# LB_i11_Pressure_Sensor-v03_4_4.net
KiCad netlist of a schematic drawn in EAGLE
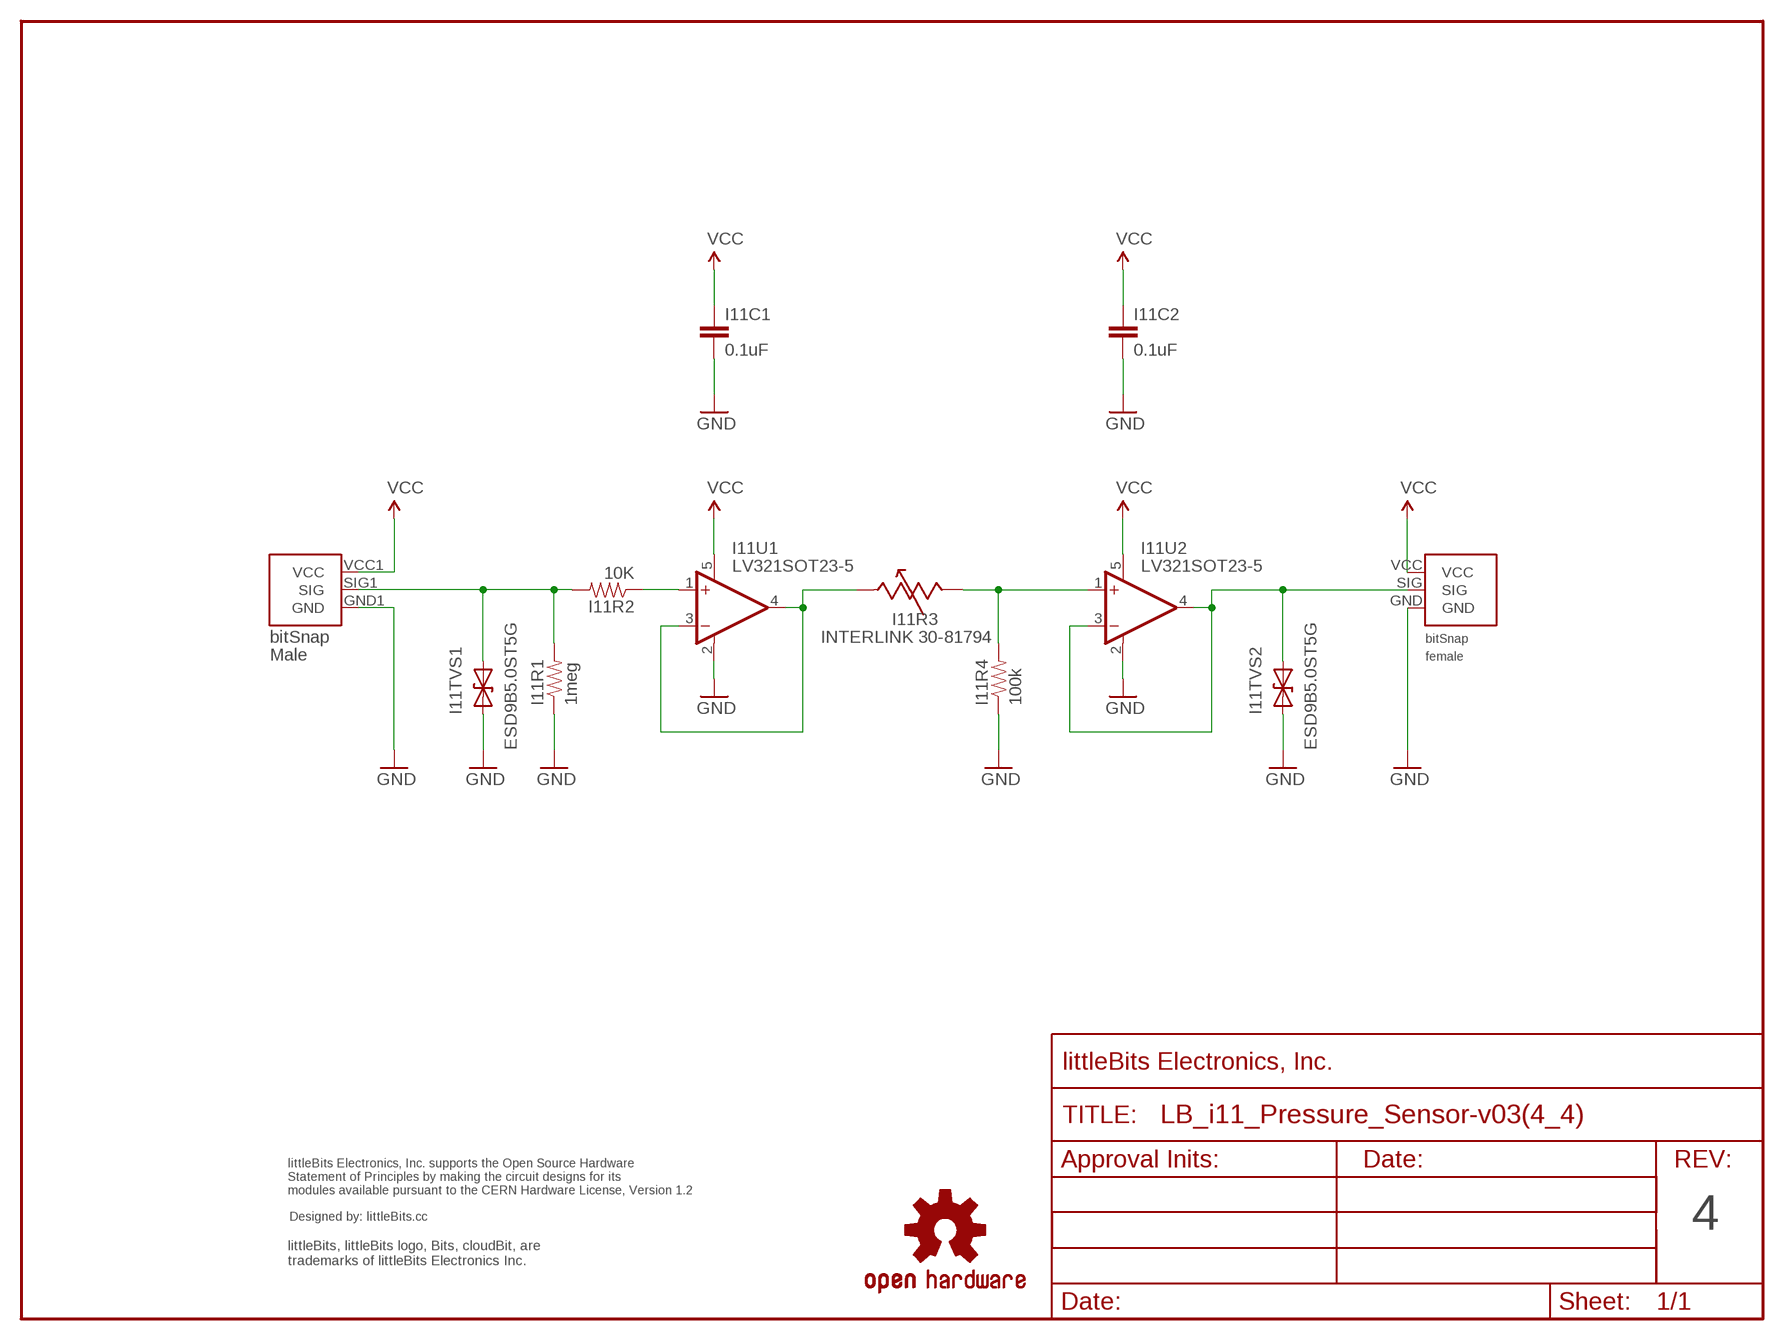
[diagram p0: schematic, sheet 1]

(export (version "E")
  (design (tool "Eeschema 10.0.6"))
  (components
    (comp (ref "FRAME1")
      (value "FRAME-LETTER-OHWOHW")
      (footprint "eagle-import:FABDWG01-OHW")
      (libsource (lib "eagle-import") (part "FRAME-LETTER-OHWOHW"))
    )
    (comp (ref "I11BSF1")
      (value "BITSNAP_V03_FEMALE")
      (footprint "eagle-import:BITSNAP_V03_FEMALE")
      (libsource (lib "eagle-import") (part "BITSNAP_V03_FEMALE"))
    )
    (comp (ref "I11BSM1")
      (value "BITSNAP_V03_MALE")
      (footprint "eagle-import:BITSNAP_V03_MALE")
      (libsource (lib "eagle-import") (part "BITSNAP_V03_MALE"))
    )
    (comp (ref "I11C1")
      (value "0.1uF")
      (footprint "eagle-import:0603-CAP")
      (libsource (lib "eagle-import") (part "CAP0603-CAP"))
    )
    (comp (ref "I11C2")
      (value "0.1uF")
      (footprint "eagle-import:0603-CAP")
      (libsource (lib "eagle-import") (part "CAP0603-CAP"))
    )
    (comp (ref "I11R1")
      (value "1meg")
      (footprint "eagle-import:RES-0603")
      (libsource (lib "eagle-import") (part "RESISTOR0603"))
    )
    (comp (ref "I11R2")
      (value "10K")
      (footprint "eagle-import:RES-0603")
      (libsource (lib "eagle-import") (part "RESISTOR0603"))
    )
    (comp (ref "I11R3")
      (value "INTERLINK 30-81794")
      (footprint "eagle-import:FSR-SMD")
      (libsource (lib "eagle-import") (part "FSR-SMD"))
    )
    (comp (ref "I11R4")
      (value "100k")
      (footprint "eagle-import:0603-RES")
      (libsource (lib "eagle-import") (part "RESISTOR0603-RES"))
    )
    (comp (ref "I11TVS1")
      (value "ESD9B5.0ST5G")
      (footprint "eagle-import:SOD-923")
      (fields (field (name "LB_PN") "?") (field (name "V_CLAMP") "?") (field (name "V_OPERATION") "5V"))
      (libsource (lib "eagle-import") (part "DIODE-TVSSOD-923"))
    )
    (comp (ref "I11TVS2")
      (value "ESD9B5.0ST5G")
      (footprint "eagle-import:SOD-923")
      (fields (field (name "LB_PN") "?") (field (name "V_CLAMP") "?") (field (name "V_OPERATION") "5V"))
      (libsource (lib "eagle-import") (part "DIODE-TVSSOD-923"))
    )
    (comp (ref "I11U1")
      (value "LV321SOT23-5")
      (footprint "eagle-import:SOT23-5")
      (libsource (lib "eagle-import") (part "LV321SOT23-5"))
    )
    (comp (ref "I11U2")
      (value "LV321SOT23-5")
      (footprint "eagle-import:SOT23-5")
      (libsource (lib "eagle-import") (part "LV321SOT23-5"))
    )
    (comp (ref "U$1")
      (value "OSHW-LOGOL")
      (footprint "eagle-import:OSHW-LOGO-L")
      (libsource (lib "eagle-import") (part "OSHW-LOGOL"))
    )
    (comp (ref "U$7")
      (value "LB_CREDITS")
      (footprint "eagle-import:OSHWCREDIT")
      (libsource (lib "eagle-import") (part "LB_CREDITS"))
    )
  )
  (nets
    (net (code "1") (name "GND") (class "Default")
      (node (ref "I11BSF1") (pin "GND") (pinfunction "GND_GND") (pintype "bidirectional"))
      (node (ref "I11BSM1") (pin "GND1") (pinfunction "GND_GND1") (pintype "bidirectional"))
      (node (ref "I11C1") (pin "2") (pinfunction "2_2") (pintype "passive"))
      (node (ref "I11C2") (pin "2") (pinfunction "2_2") (pintype "passive"))
      (node (ref "I11R1") (pin "1") (pinfunction "1_1") (pintype "passive"))
      (node (ref "I11R4") (pin "1") (pinfunction "1_1") (pintype "passive"))
      (node (ref "I11TVS1") (pin "1") (pinfunction "A_1") (pintype "passive"))
      (node (ref "I11TVS2") (pin "1") (pinfunction "A_1") (pintype "passive"))
      (node (ref "I11U1") (pin "2") (pinfunction "V-_2") (pintype "power_in"))
      (node (ref "I11U2") (pin "2") (pinfunction "V-_2") (pintype "power_in"))
    )
    (net (code "2") (name "Net-(I11BSM1-SIG)") (class "Default")
      (node (ref "I11BSM1") (pin "SIG1") (pinfunction "SIG_SIG1") (pintype "bidirectional"))
      (node (ref "I11R1") (pin "2") (pinfunction "2_2") (pintype "passive"))
      (node (ref "I11R2") (pin "2") (pinfunction "2_2") (pintype "passive"))
      (node (ref "I11TVS1") (pin "2") (pinfunction "C_2") (pintype "passive"))
    )
    (net (code "3") (name "Net-(I11R3-A)") (class "Default")
      (node (ref "I11R3") (pin "2") (pinfunction "A_2") (pintype "passive"))
      (node (ref "I11R4") (pin "2") (pinfunction "2_2") (pintype "passive"))
      (node (ref "I11U2") (pin "1") (pinfunction "+IN_1") (pintype "input"))
    )
    (net (code "4") (name "Net-(I11TVS2-C)") (class "Default")
      (node (ref "I11BSF1") (pin "SIG") (pinfunction "SIG_SIG") (pintype "bidirectional"))
      (node (ref "I11TVS2") (pin "2") (pinfunction "C_2") (pintype "passive"))
      (node (ref "I11U2") (pin "3") (pinfunction "-IN_3") (pintype "input"))
      (node (ref "I11U2") (pin "4") (pinfunction "OUT_4") (pintype "output"))
    )
    (net (code "5") (name "Net-(I11U1-+IN)") (class "Default")
      (node (ref "I11R2") (pin "1") (pinfunction "1_1") (pintype "passive"))
      (node (ref "I11U1") (pin "1") (pinfunction "+IN_1") (pintype "input"))
    )
    (net (code "6") (name "Net-(I11U1--IN)") (class "Default")
      (node (ref "I11R3") (pin "1") (pinfunction "1_1") (pintype "passive"))
      (node (ref "I11U1") (pin "3") (pinfunction "-IN_3") (pintype "input"))
      (node (ref "I11U1") (pin "4") (pinfunction "OUT_4") (pintype "output"))
    )
    (net (code "7") (name "VCC") (class "Default")
      (node (ref "I11BSF1") (pin "VCC") (pinfunction "VCC_VCC") (pintype "bidirectional"))
      (node (ref "I11BSM1") (pin "VCC1") (pinfunction "VCC_VCC1") (pintype "bidirectional"))
      (node (ref "I11C1") (pin "1") (pinfunction "1_1") (pintype "passive"))
      (node (ref "I11C2") (pin "1") (pinfunction "1_1") (pintype "passive"))
      (node (ref "I11U1") (pin "5") (pinfunction "V+_5") (pintype "power_in"))
      (node (ref "I11U2") (pin "5") (pinfunction "V+_5") (pintype "power_in"))
    )
  )
)
